# ERA_battery.net
KiCad netlist of a schematic drawn in EasyEDA
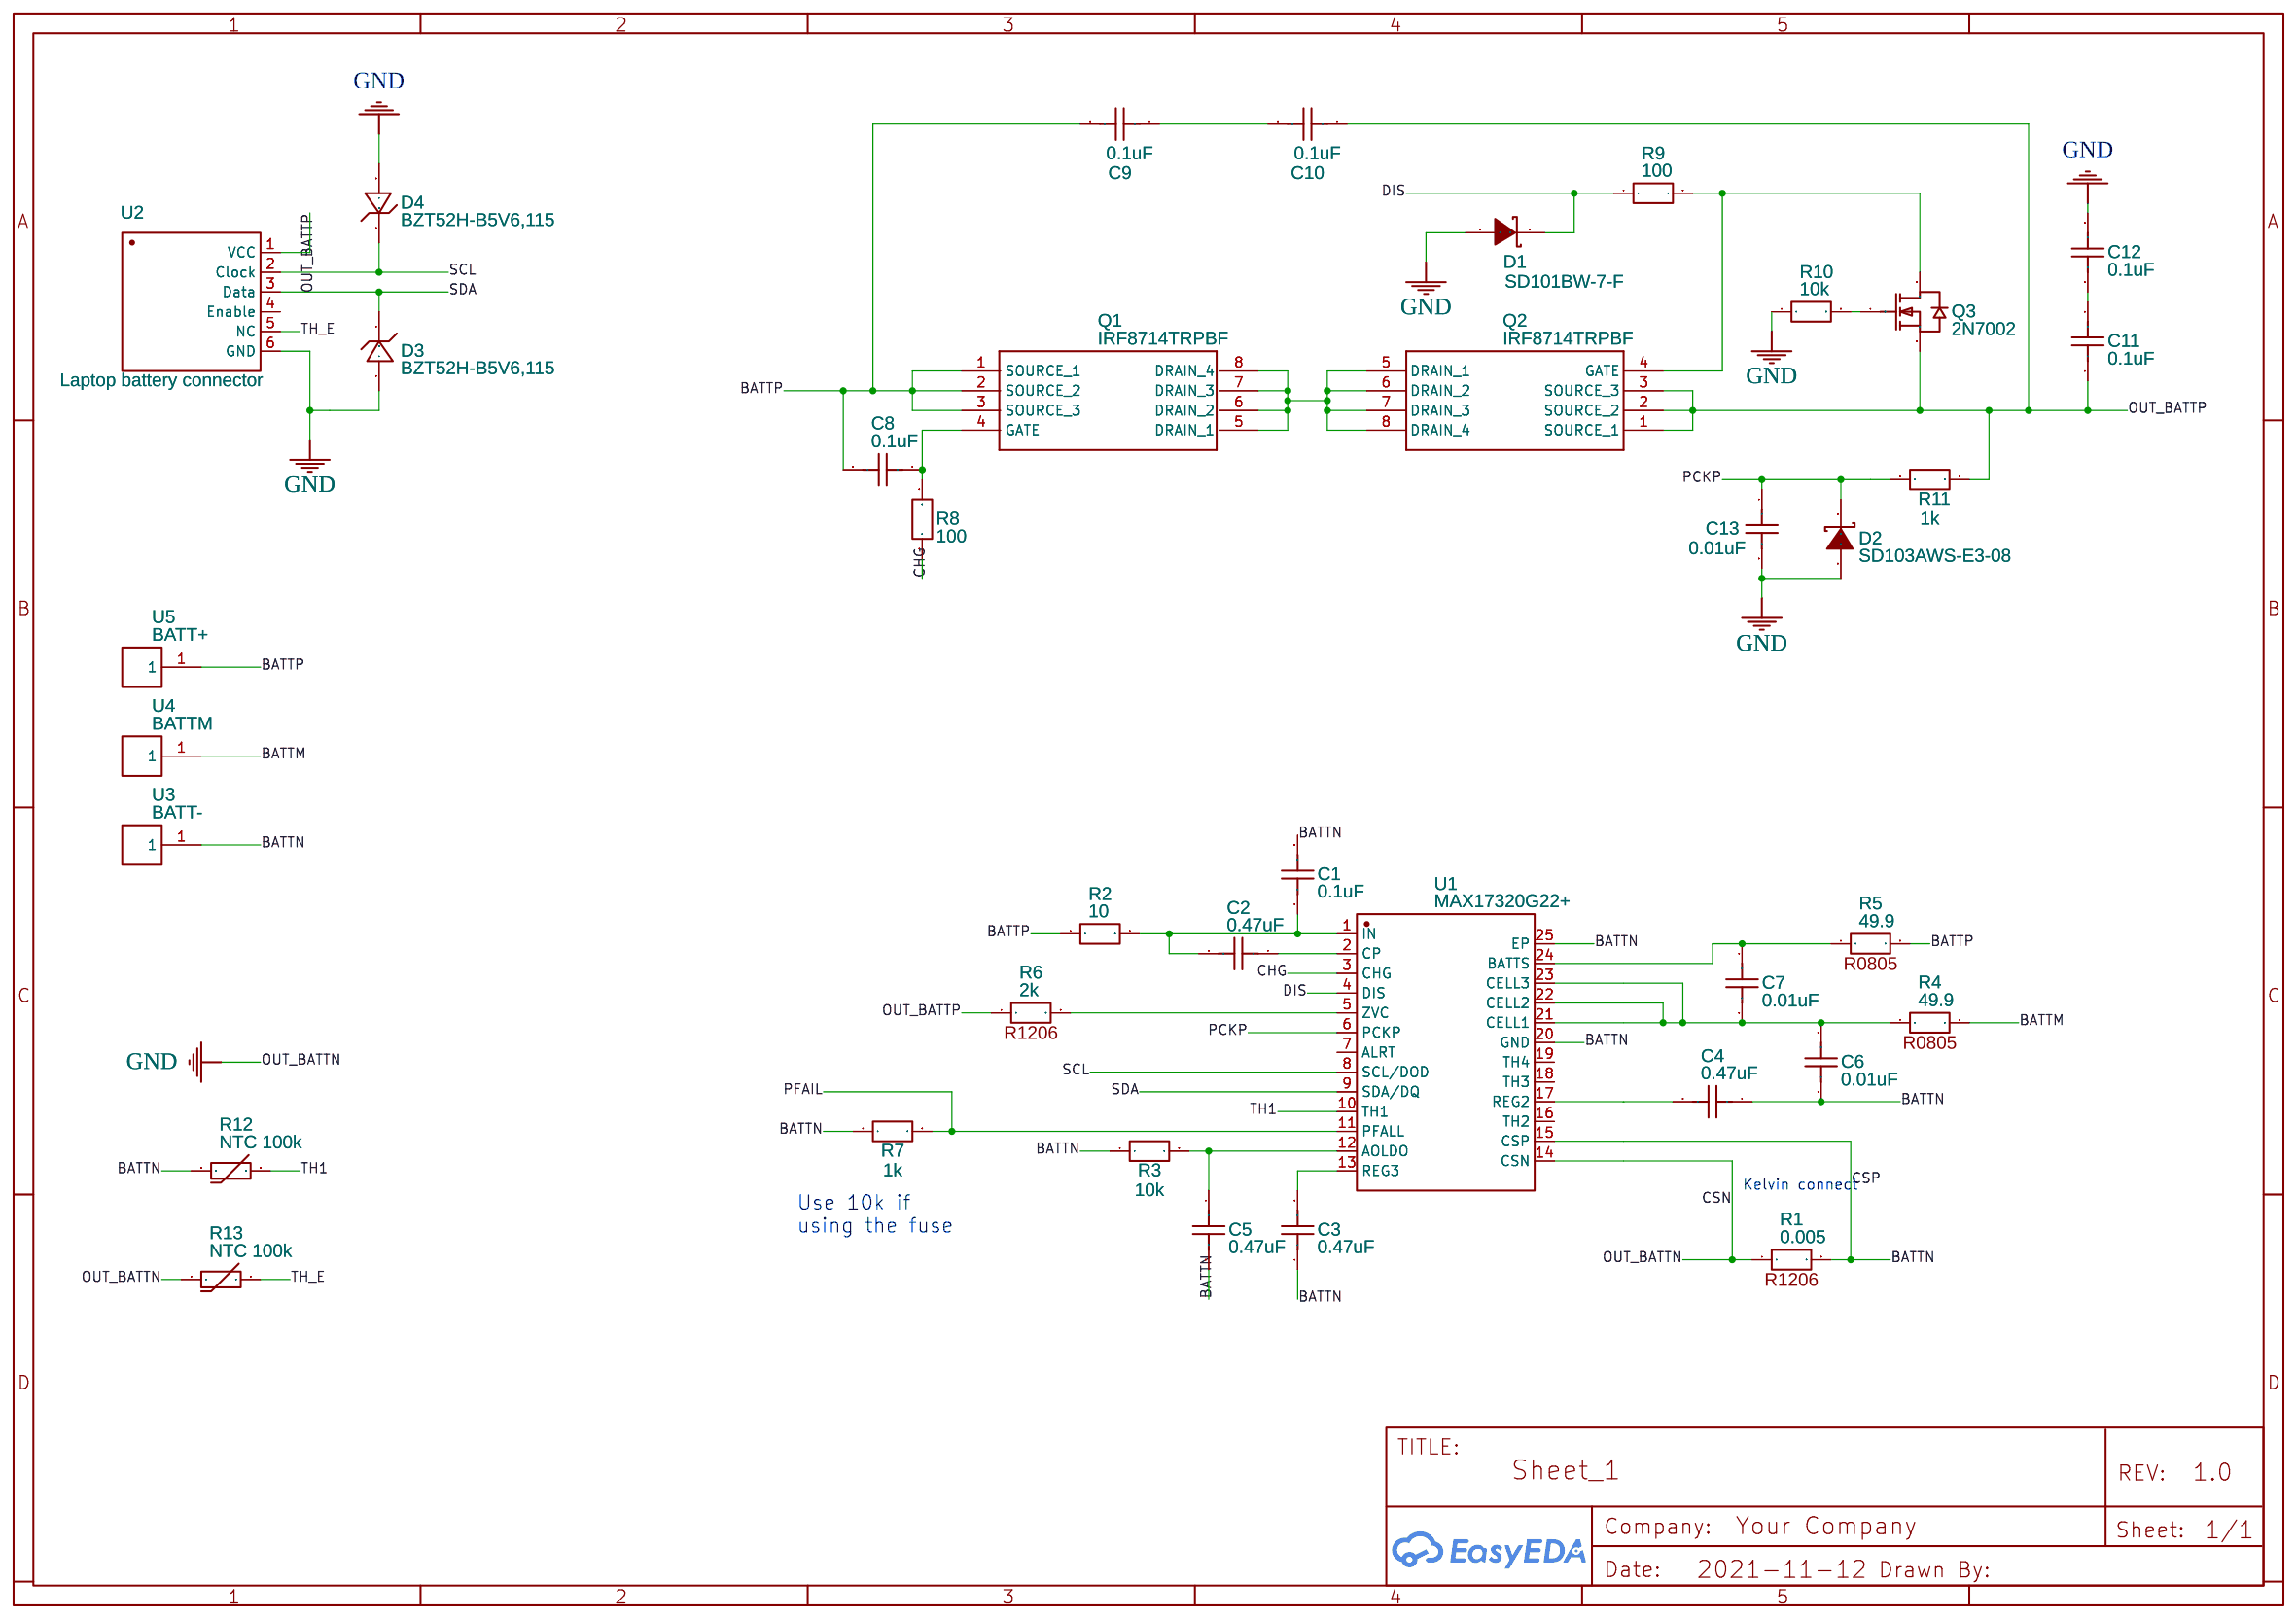
[diagram p0: schematic sheet]

(export (version "E")
  (design (tool "Eeschema 10.0.6"))
  (components
    (comp (ref "C1") (value "0.1uF") (libsource (lib "") (part "C_0603_US_2")))
    (comp (ref "C2") (value "0.47uF") (libsource (lib "") (part "C_0603_US_1")))
    (comp (ref "C3") (value "0.47uF") (libsource (lib "") (part "C_0603_US_2")))
    (comp (ref "C4") (value "0.47uF") (libsource (lib "") (part "C_0603_US_1")))
    (comp (ref "C5") (value "0.47uF") (libsource (lib "") (part "C_0603_US")))
    (comp (ref "C6") (value "0.01uF") (libsource (lib "") (part "C_0603_US_2")))
    (comp (ref "C7") (value "0.01uF") (libsource (lib "") (part "C_0603_US")))
    (comp (ref "C8") (value "0.1uF") (libsource (lib "") (part "C_0603_US_1")))
    (comp (ref "C9") (value "0.1uF") (libsource (lib "") (part "C_0603_US_1")))
    (comp (ref "C10") (value "0.1uF") (libsource (lib "") (part "C_0603_US_1")))
    (comp (ref "C11") (value "0.1uF") (libsource (lib "") (part "C_0603_US_2")))
    (comp (ref "C12") (value "0.1uF") (libsource (lib "") (part "C_0603_US_2")))
    (comp (ref "C13") (value "0.01uF") (libsource (lib "") (part "C_0603_US")))
    (comp (ref "D1")
      (value "SD101BW-7-F")
      (fields
        (field (name "BOM_Manufacturer Part") "SD101BWS-7-F")
        (field (name "BOM_Supplier Part") "C526757")
      )
      (libsource (lib "") (part "SD101BWS-7-F"))
    )
    (comp (ref "D2")
      (value "SD103AWS-E3-08")
      (fields (field (name "BOM_Supplier Part") "C142592"))
      (libsource (lib "") (part "SD103AWS-E3-08"))
    )
    (comp (ref "D3")
      (value "BZT52H-B5V6,115")
      (fields (field (name "BOM_Supplier Part") "C426804"))
      (libsource (lib "") (part "BZT52H-B5V6,115"))
    )
    (comp (ref "D4")
      (value "BZT52H-B5V6,115")
      (fields (field (name "BOM_Supplier Part") "C426804"))
      (libsource (lib "") (part "BZT52H-B5V6,115_1"))
    )
    (comp (ref "Q1") (value "IRF8714TRPBF") (libsource (lib "") (part "IRF8714TRPBF_1")))
    (comp (ref "Q2") (value "IRF8714TRPBF") (libsource (lib "") (part "IRF8714TRPBF")))
    (comp (ref "Q3")
      (value "2N7002")
      (fields (field (name "BOM_Supplier Part") "C8545"))
      (libsource (lib "") (part "2N7002"))
    )
    (comp (ref "R1") (value "0.005") (libsource (lib "") (part "R_1206_EU")))
    (comp (ref "R2") (value "10") (libsource (lib "") (part "R_0603_EU")))
    (comp (ref "R3") (value "10k") (libsource (lib "") (part "R_0603_EU")))
    (comp (ref "R4") (value "49.9") (libsource (lib "") (part "R_0805_EU")))
    (comp (ref "R5")
      (value "49.9")
      (fields
        (field (name "BOM_Manufacturer Part") "RMC080549.91%N")
        (field (name "BOM_Supplier Part") "C269747")
      )
      (libsource (lib "") (part "R_0805_EU"))
    )
    (comp (ref "R6") (value "2k") (libsource (lib "") (part "R_1210_EU")))
    (comp (ref "R7") (value "1k") (libsource (lib "") (part "R_0603_EU")))
    (comp (ref "R8") (value "100") (libsource (lib "") (part "R_0603_EU_1")))
    (comp (ref "R9") (value "100") (libsource (lib "") (part "R_0603_EU")))
    (comp (ref "R10") (value "10k") (libsource (lib "") (part "R_0603_EU")))
    (comp (ref "R11") (value "1k") (libsource (lib "") (part "R_0603_EU")))
    (comp (ref "R12")
      (value "NTC 100k")
      (fields
        (field (name "BOM_Manufacturer Part") "CMFB102J3200HANT")
        (field (name "BOM_Supplier Part") "C75245")
      )
      (libsource (lib "") (part "CMFB102J3200HANT"))
    )
    (comp (ref "R13")
      (value "NTC 100k")
      (fields
        (field (name "BOM_Manufacturer Part") "CMFB102J3200HANT")
        (field (name "BOM_Supplier Part") "C75245")
      )
      (libsource (lib "") (part "CMFB102J3200HANT"))
    )
    (comp (ref "U1")
      (value "MAX17320G22+")
      (fields (field (name "BOM_Supplier Part") "C2914309"))
      (libsource (lib "") (part "MAX17320G22+"))
    )
    (comp (ref "U2")
      (value "Laptop battery connector")
      (libsource (lib "") (part "Laptop battery connector"))
    )
    (comp (ref "U3") (value "BATT-") (libsource (lib "") (part "PAD1")))
    (comp (ref "U4") (value "BATTM") (libsource (lib "") (part "PAD1")))
    (comp (ref "U5") (value "BATT+") (libsource (lib "") (part "PAD1")))
  )
  (nets
    (net (code "1") (name "/BATTM") (class "Default")
      (node (ref "R4") (pin "2") (pinfunction "2_2") (pintype "unspecified"))
      (node (ref "U4") (pin "1") (pinfunction "1_1") (pintype "unspecified"))
    )
    (net (code "2") (name "/BATTN") (class "Default")
      (node (ref "C1") (pin "2") (pinfunction "2_2") (pintype "unspecified"))
      (node (ref "C3") (pin "1") (pinfunction "1_1") (pintype "unspecified"))
      (node (ref "C4") (pin "1") (pinfunction "1_1") (pintype "unspecified"))
      (node (ref "C5") (pin "2") (pinfunction "2_2") (pintype "unspecified"))
      (node (ref "C6") (pin "1") (pinfunction "1_1") (pintype "unspecified"))
      (node (ref "R1") (pin "2") (pinfunction "2_2") (pintype "unspecified"))
      (node (ref "R12") (pin "1") (pinfunction "1_1") (pintype "input"))
      (node (ref "R3") (pin "1") (pinfunction "1_1") (pintype "unspecified"))
      (node (ref "R7") (pin "1") (pinfunction "1_1") (pintype "unspecified"))
      (node (ref "U1") (pin "15") (pinfunction "CSP_15") (pintype "unspecified"))
      (node (ref "U1") (pin "20") (pinfunction "GND_20") (pintype "unspecified"))
      (node (ref "U1") (pin "25") (pinfunction "EP_25") (pintype "unspecified"))
      (node (ref "U3") (pin "1") (pinfunction "1_1") (pintype "unspecified"))
    )
    (net (code "3") (name "/BATTP") (class "Default")
      (node (ref "C8") (pin "2") (pinfunction "2_2") (pintype "unspecified"))
      (node (ref "C9") (pin "2") (pinfunction "2_2") (pintype "unspecified"))
      (node (ref "Q1") (pin "1") (pinfunction "SOURCE_1_1") (pintype "bidirectional"))
      (node (ref "Q1") (pin "2") (pinfunction "SOURCE_2_2") (pintype "bidirectional"))
      (node (ref "Q1") (pin "3") (pinfunction "SOURCE_3_3") (pintype "bidirectional"))
      (node (ref "R2") (pin "1") (pinfunction "1_1") (pintype "unspecified"))
      (node (ref "R5") (pin "2") (pinfunction "2_2") (pintype "unspecified"))
      (node (ref "U5") (pin "1") (pinfunction "1_1") (pintype "unspecified"))
    )
    (net (code "4") (name "/CHG") (class "Default")
      (node (ref "R8") (pin "1") (pinfunction "1_1") (pintype "unspecified"))
      (node (ref "U1") (pin "3") (pinfunction "CHG_3") (pintype "unspecified"))
    )
    (net (code "5") (name "/DIS") (class "Default")
      (node (ref "D1") (pin "1") (pinfunction "C_1") (pintype "unspecified"))
      (node (ref "R9") (pin "1") (pinfunction "1_1") (pintype "unspecified"))
      (node (ref "U1") (pin "4") (pinfunction "DIS_4") (pintype "unspecified"))
    )
    (net (code "6") (name "/OUT_BATTP") (class "Default")
      (node (ref "C10") (pin "1") (pinfunction "1_1") (pintype "unspecified"))
      (node (ref "C11") (pin "1") (pinfunction "1_1") (pintype "unspecified"))
      (node (ref "Q2") (pin "1") (pinfunction "SOURCE_1_1") (pintype "bidirectional"))
      (node (ref "Q2") (pin "2") (pinfunction "SOURCE_2_2") (pintype "bidirectional"))
      (node (ref "Q2") (pin "3") (pinfunction "SOURCE_3_3") (pintype "bidirectional"))
      (node (ref "Q3") (pin "2") (pinfunction "S_2") (pintype "unspecified"))
      (node (ref "R11") (pin "2") (pinfunction "2_2") (pintype "unspecified"))
      (node (ref "R6") (pin "1") (pinfunction "1_1") (pintype "unspecified"))
      (node (ref "U2") (pin "1") (pinfunction "VCC_1") (pintype "unspecified"))
    )
    (net (code "7") (name "/PCKP") (class "Default")
      (node (ref "C13") (pin "1") (pinfunction "1_1") (pintype "unspecified"))
      (node (ref "D2") (pin "1") (pinfunction "K_1") (pintype "unspecified"))
      (node (ref "R11") (pin "1") (pinfunction "1_1") (pintype "unspecified"))
      (node (ref "U1") (pin "6") (pinfunction "PCKP_6") (pintype "unspecified"))
    )
    (net (code "8") (name "/PFAIL") (class "Default")
      (node (ref "R7") (pin "2") (pinfunction "2_2") (pintype "unspecified"))
      (node (ref "U1") (pin "11") (pinfunction "PFALL_11") (pintype "unspecified"))
    )
    (net (code "9") (name "/SCL") (class "Default")
      (node (ref "D4") (pin "1") (pinfunction "C_1") (pintype "unspecified"))
      (node (ref "U1") (pin "8") (pinfunction "SCL/DOD_8") (pintype "unspecified"))
      (node (ref "U2") (pin "2") (pinfunction "Clock_2") (pintype "unspecified"))
    )
    (net (code "10") (name "/SDA") (class "Default")
      (node (ref "D3") (pin "1") (pinfunction "C_1") (pintype "unspecified"))
      (node (ref "U1") (pin "9") (pinfunction "SDA/DQ_9") (pintype "unspecified"))
      (node (ref "U2") (pin "3") (pinfunction "Data_3") (pintype "unspecified"))
    )
    (net (code "11") (name "/TH1") (class "Default")
      (node (ref "R12") (pin "2") (pinfunction "2_2") (pintype "input"))
      (node (ref "U1") (pin "10") (pinfunction "TH1_10") (pintype "unspecified"))
    )
    (net (code "12") (name "/TH_E") (class "Default")
      (node (ref "R13") (pin "2") (pinfunction "2_2") (pintype "input"))
      (node (ref "U2") (pin "5") (pinfunction "NC_5") (pintype "unspecified"))
    )
    (net (code "13") (name "GND") (class "Default")
      (node (ref "C12") (pin "2") (pinfunction "2_2") (pintype "unspecified"))
      (node (ref "C13") (pin "2") (pinfunction "2_2") (pintype "unspecified"))
      (node (ref "D1") (pin "2") (pinfunction "A_2") (pintype "unspecified"))
      (node (ref "D2") (pin "2") (pinfunction "A_2") (pintype "unspecified"))
      (node (ref "D3") (pin "2") (pinfunction "A_2") (pintype "unspecified"))
      (node (ref "D4") (pin "2") (pinfunction "A_2") (pintype "unspecified"))
      (node (ref "R1") (pin "1") (pinfunction "1_1") (pintype "unspecified"))
      (node (ref "R10") (pin "1") (pinfunction "1_1") (pintype "unspecified"))
      (node (ref "R13") (pin "1") (pinfunction "1_1") (pintype "input"))
      (node (ref "U1") (pin "14") (pinfunction "CSN_14") (pintype "unspecified"))
      (node (ref "U2") (pin "6") (pinfunction "GND_6") (pintype "unspecified"))
    )
    (net (code "14") (name "Net-(C10-Pad2)") (class "Default")
      (node (ref "C10") (pin "2") (pinfunction "2_2") (pintype "unspecified"))
      (node (ref "C9") (pin "1") (pinfunction "1_1") (pintype "unspecified"))
    )
    (net (code "15") (name "Net-(C11-Pad2)") (class "Default")
      (node (ref "C11") (pin "2") (pinfunction "2_2") (pintype "unspecified"))
      (node (ref "C12") (pin "1") (pinfunction "1_1") (pintype "unspecified"))
    )
    (net (code "16") (name "Net-(Q1-DRAIN_1)") (class "Default")
      (node (ref "Q1") (pin "5") (pinfunction "DRAIN_1_5") (pintype "bidirectional"))
      (node (ref "Q1") (pin "6") (pinfunction "DRAIN_2_6") (pintype "bidirectional"))
      (node (ref "Q1") (pin "7") (pinfunction "DRAIN_3_7") (pintype "bidirectional"))
      (node (ref "Q1") (pin "8") (pinfunction "DRAIN_4_8") (pintype "bidirectional"))
      (node (ref "Q2") (pin "5") (pinfunction "DRAIN_1_5") (pintype "bidirectional"))
      (node (ref "Q2") (pin "6") (pinfunction "DRAIN_2_6") (pintype "bidirectional"))
      (node (ref "Q2") (pin "7") (pinfunction "DRAIN_3_7") (pintype "bidirectional"))
      (node (ref "Q2") (pin "8") (pinfunction "DRAIN_4_8") (pintype "bidirectional"))
    )
    (net (code "17") (name "Net-(Q1-GATE)") (class "Default")
      (node (ref "C8") (pin "1") (pinfunction "1_1") (pintype "unspecified"))
      (node (ref "Q1") (pin "4") (pinfunction "GATE_4") (pintype "bidirectional"))
      (node (ref "R8") (pin "2") (pinfunction "2_2") (pintype "unspecified"))
    )
    (net (code "18") (name "Net-(Q2-GATE)") (class "Default")
      (node (ref "Q2") (pin "4") (pinfunction "GATE_4") (pintype "bidirectional"))
      (node (ref "Q3") (pin "3") (pinfunction "D_3") (pintype "unspecified"))
      (node (ref "R9") (pin "2") (pinfunction "2_2") (pintype "unspecified"))
    )
    (net (code "19") (name "Net-(Q3-G)") (class "Default")
      (node (ref "Q3") (pin "1") (pinfunction "G_1") (pintype "unspecified"))
      (node (ref "R10") (pin "2") (pinfunction "2_2") (pintype "unspecified"))
    )
    (net (code "20") (name "Net-(U1-AOLDO)") (class "Default")
      (node (ref "C5") (pin "1") (pinfunction "1_1") (pintype "unspecified"))
      (node (ref "R3") (pin "2") (pinfunction "2_2") (pintype "unspecified"))
      (node (ref "U1") (pin "12") (pinfunction "AOLDO_12") (pintype "unspecified"))
    )
    (net (code "21") (name "Net-(U1-BATTS)") (class "Default")
      (node (ref "C7") (pin "1") (pinfunction "1_1") (pintype "unspecified"))
      (node (ref "R5") (pin "1") (pinfunction "1_1") (pintype "unspecified"))
      (node (ref "U1") (pin "24") (pinfunction "BATTS_24") (pintype "unspecified"))
    )
    (net (code "22") (name "Net-(U1-CELL1)") (class "Default")
      (node (ref "C6") (pin "2") (pinfunction "2_2") (pintype "unspecified"))
      (node (ref "C7") (pin "2") (pinfunction "2_2") (pintype "unspecified"))
      (node (ref "R4") (pin "1") (pinfunction "1_1") (pintype "unspecified"))
      (node (ref "U1") (pin "21") (pinfunction "CELL1_21") (pintype "unspecified"))
      (node (ref "U1") (pin "22") (pinfunction "CELL2_22") (pintype "unspecified"))
      (node (ref "U1") (pin "23") (pinfunction "CELL3_23") (pintype "unspecified"))
    )
    (net (code "23") (name "Net-(U1-CP)") (class "Default")
      (node (ref "C2") (pin "1") (pinfunction "1_1") (pintype "unspecified"))
      (node (ref "U1") (pin "2") (pinfunction "CP_2") (pintype "unspecified"))
    )
    (net (code "24") (name "Net-(U1-IN)") (class "Default")
      (node (ref "C1") (pin "1") (pinfunction "1_1") (pintype "unspecified"))
      (node (ref "C2") (pin "2") (pinfunction "2_2") (pintype "unspecified"))
      (node (ref "R2") (pin "2") (pinfunction "2_2") (pintype "unspecified"))
      (node (ref "U1") (pin "1") (pinfunction "IN_1") (pintype "unspecified"))
    )
    (net (code "25") (name "Net-(U1-REG2)") (class "Default")
      (node (ref "C4") (pin "2") (pinfunction "2_2") (pintype "unspecified"))
      (node (ref "U1") (pin "17") (pinfunction "REG2_17") (pintype "unspecified"))
    )
    (net (code "26") (name "Net-(U1-REG3)") (class "Default")
      (node (ref "C3") (pin "2") (pinfunction "2_2") (pintype "unspecified"))
      (node (ref "U1") (pin "13") (pinfunction "REG3_13") (pintype "unspecified"))
    )
    (net (code "27") (name "Net-(U1-ZVC)") (class "Default")
      (node (ref "R6") (pin "2") (pinfunction "2_2") (pintype "unspecified"))
      (node (ref "U1") (pin "5") (pinfunction "ZVC_5") (pintype "unspecified"))
    )
    (net (code "28") (name "unconnected-(U1-ALRT-Pad7)") (class "Default")
      (node (ref "U1") (pin "7") (pinfunction "ALRT_7") (pintype "unspecified"))
    )
    (net (code "29") (name "unconnected-(U1-TH2-Pad16)") (class "Default")
      (node (ref "U1") (pin "16") (pinfunction "TH2_16") (pintype "unspecified"))
    )
    (net (code "30") (name "unconnected-(U1-TH3-Pad18)") (class "Default")
      (node (ref "U1") (pin "18") (pinfunction "TH3_18") (pintype "unspecified"))
    )
    (net (code "31") (name "unconnected-(U1-TH4-Pad19)") (class "Default")
      (node (ref "U1") (pin "19") (pinfunction "TH4_19") (pintype "unspecified"))
    )
    (net (code "32") (name "unconnected-(U2-Enable-Pad4)") (class "Default")
      (node (ref "U2") (pin "4") (pinfunction "Enable_4") (pintype "unspecified"))
    )
  )
)
